# SDP21_Daughter_Board_Schematic_REV1.net
KiCad netlist of a schematic drawn in Altium Designer
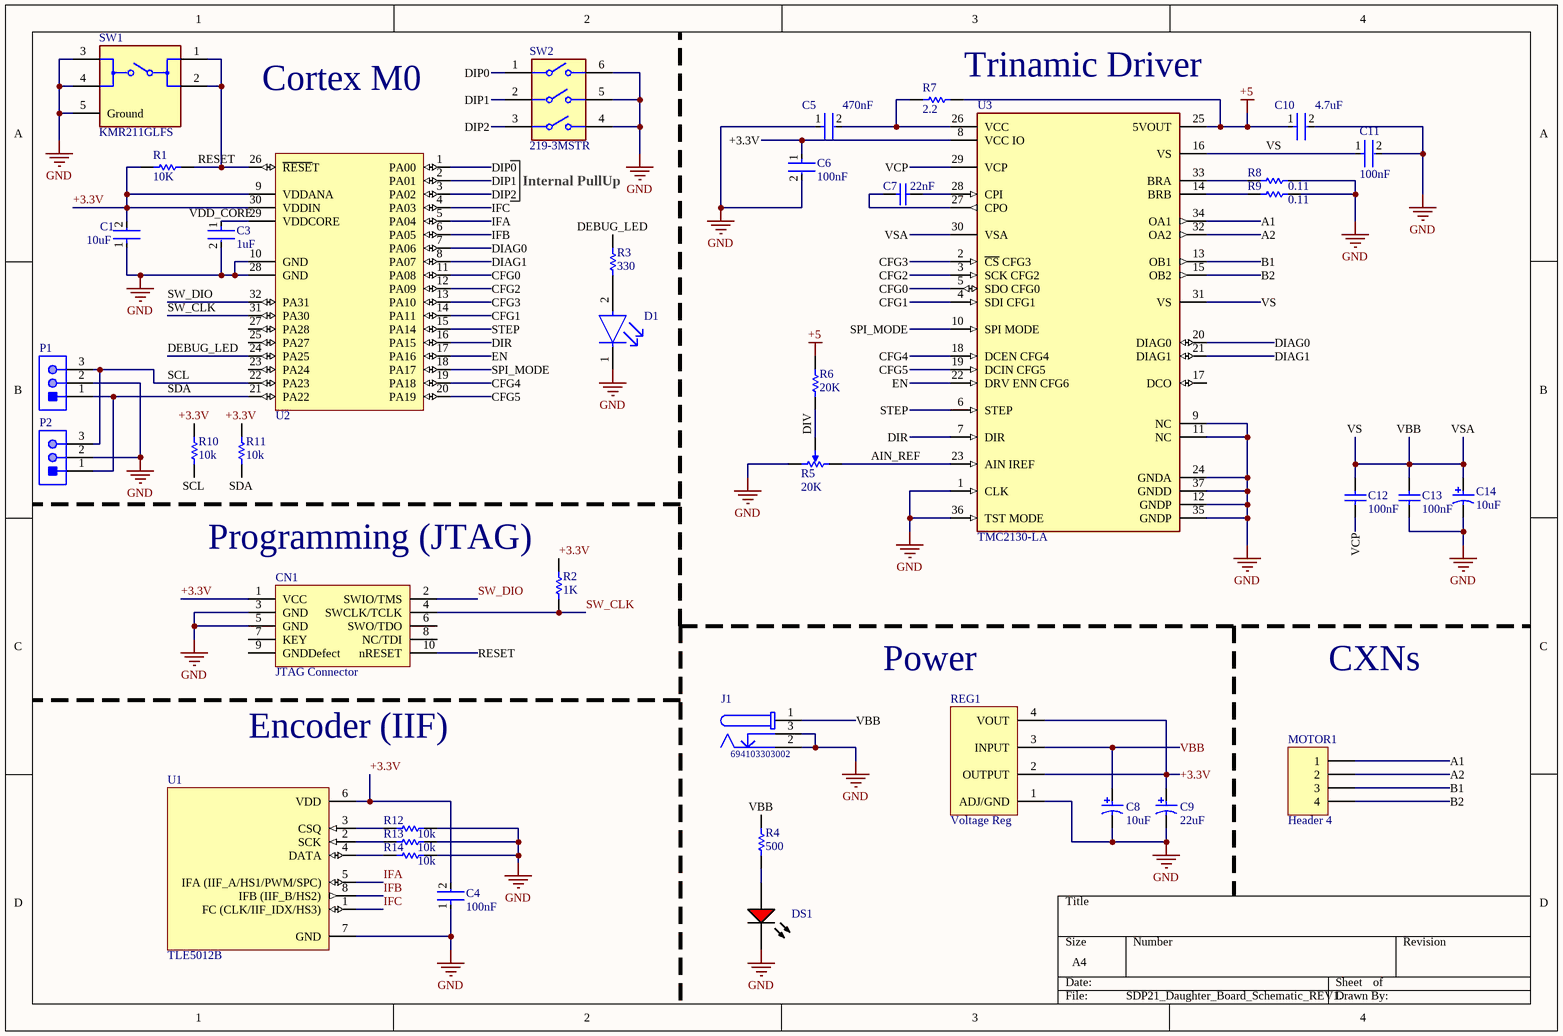
[diagram p0: SDP21_Daughter_Board_Schematic_REV1.SchDoc]

(export (version "E")
  (design (tool "Eeschema 10.0.6"))
  (components
    (comp (ref "C1")
      (value "10uF")
      (footprint "FP-GRM188-0_1-e0_2_0_55-IPC_A")
      (description "Chip Multilayer Ceramic Capacitors for General Purpose, 0603, 10uF, X5R, 15%, 20%, 6.3V")
      (fields (field (name "VOLTAGE") "6.3V") (field (name "TOLERANCE") "20%"))
      (libsource (lib "Altium Content Vault") (part "02cd4be3c70576c341d710602a673aa"))
    )
    (comp (ref "C3")
      (value "1uF")
      (footprint "FP-CC0603-DA-MFG")
      (description "CAP CER 1UF 16V X7R 0603")
      (fields (field (name "TOLERANCE") "0.1") (field (name "MANUFACTURER") "YAGEO"))
      (libsource (lib "Altium Content Vault") (part "11868f565c42a9108669ba33697ecf6"))
    )
    (comp (ref "C4")
      (value "100nF")
      (footprint "FP-CGA3E-0_3-0_1-IPC_A")
      (description "Cap Ceramic 100nF 50V X7R 10% Pad SMD 0603 +125°C Automotive T/R")
      (fields (field (name "VOLTAGE") "50V") (field (name "TOLERANCE") "10%"))
      (libsource (lib "Altium Content Vault") (part "b4654b650e69147ec39a6b967a45e02"))
    )
    (comp (ref "C5")
      (value "470nF")
      (footprint "FP-CC0603-DA-MFG")
      (description "CAP CER 0.47UF 10V X7R 0603")
      (fields (field (name "MANUFACTURER PART NUMBER") "CC0603KRX7R6BB474") (field (name "TOLERANCE") "0.1"))
      (libsource (lib "Altium Content Vault") (part "11868f565c42a9108669ba33697ecf6"))
    )
    (comp (ref "C6")
      (value "100nF")
      (footprint "FP-CGA3E-0_3-0_1-IPC_A")
      (description "Cap Ceramic 100nF 100V X7S 10% Pad SMD 0603 +125°C Automotive T/R")
      (fields (field (name "TOLERANCE") "10%"))
      (libsource (lib "Altium Content Vault") (part "b4654b650e69147ec39a6b967a45e02"))
    )
    (comp (ref "C7")
      (value "22nF")
      (footprint "CAPC1608X90X35ML10T15")
      (fields (field (name "MANUFACTURER") "Murata") (field (name "PART NUMBER") "GRM188R71H223KA01D"))
      (libsource (lib "Altium Content Vault") (part "CAP"))
    )
    (comp (ref "C8")
      (value "10uF")
      (footprint "KEMT-A-3216-18-2_M")
      (description "Capacitor, Tantalum, 10 uF, +/- 10%, 10 V, -55 to 125 degC, 2-Pin SMD (1206), RoHS, Tape and Reel")
      (fields (field (name "TOLERANCE") "±10%") (field (name "MANUFACTURER") "Kemet"))
      (libsource (lib "Altium Content Vault") (part "CAP-P-2"))
    )
    (comp (ref "C9")
      (value "22uF")
      (footprint "AVX-TAJ-A-2_L")
      (description "Chip Capacitor, 22 uF, +/- 10%, 10 V, -55 to 125 degC, 1206 (3216 Metric), RoHS, Tape and Reel")
      (fields (field (name "MANUFACTURER") "AVX") (field (name "TOLERANCE") "10%"))
      (libsource (lib "Altium Content Vault") (part "CAP-P-2"))
    )
    (comp (ref "C10")
      (value "4.7uF")
      (footprint "FP-GRM188-0_15-IPC_C")
      (description "Chip Multilayer Ceramic Capacitors for General Purpose, 0603, 4.7uF, X5R, 15%, 10%, 25V")
      (fields (field (name "VOLTAGE") "25V") (field (name "TOLERANCE") "10%"))
      (libsource (lib "Altium Content Vault") (part "02cd4be3c70576c341d710602a673aa"))
    )
    (comp (ref "C11")
      (value "100nF")
      (footprint "FP-CGA3E-0_3-0_1-IPC_A")
      (description "Cap Ceramic 100nF 100V X7S 10% Pad SMD 0603 +125°C Automotive T/R")
      (fields (field (name "TOLERANCE") "10%"))
      (libsource (lib "Altium Content Vault") (part "b4654b650e69147ec39a6b967a45e02"))
    )
    (comp (ref "C12")
      (value "100nF")
      (footprint "CAPC1608X90X35ML10T15")
      (description "Chip Capacitor, 0.1 uF, +/- 10%, 50 V, -55 to 125 degC, 0603 (1608 Metric), RoHS, Tape and Reel")
      (fields (field (name "TOLERANCE") "10%") (field (name "VOLTAGE") "50V"))
      (libsource (lib "Altium Content Vault") (part "CAP-NP-2"))
    )
    (comp (ref "C13")
      (value "100nF")
      (footprint "CAPC1608X90X35ML10T15")
      (description "Chip Capacitor, 0.1 uF, +/- 10%, 50 V, -55 to 125 degC, 0603 (1608 Metric), RoHS, Tape and Reel")
      (fields (field (name "TOLERANCE") "10%") (field (name "VOLTAGE") "50V"))
      (libsource (lib "Altium Content Vault") (part "CAP-NP-2"))
    )
    (comp (ref "C14")
      (value "10uF")
      (footprint "NIC-CAPA2-6.3X5.8_V")
      (fields (field (name "MANUFACTURER") "Nichicon") (field (name "PARTNUMBER") "UUD1H100MCL1GS"))
      (libsource (lib "Altium Content Vault") (part "NIC-CAP-P-2"))
    )
    (comp (ref "CN1")
      (value "JTAG Connector")
      (footprint "Header 5x2 - 50mil")
      (libsource (lib "SDP21_Symbols") (part "JTAG Connector"))
    )
    (comp (ref "D1")
      (value "APT1608LZGCK")
      (footprint "FP-APT1608LZGCK-MFG")
      (description "LED GREEN CLEAR 2SMD")
      (libsource (lib "Altium Content Vault") (part "8706943c75ba83719d021d2fdc84c58"))
    )
    (comp (ref "DS1")
      (value "TLMS1100-GS08")
      (footprint "VISH-TLMX1100_V")
      (description "LED, RED, 2.1 V, -40 to 100 degC, 2-Pin SMD (0603), RoHS, Tape and Reel")
      (fields (field (name "TOLERANCE") "5%"))
      (libsource (lib "Altium Content Vault") (part "LED-RED-AK-2"))
    )
    (comp (ref "J1")
      (value "694103303002")
      (footprint "694103303002")
      (description "DC Power Jack Connector WR-DC, Male, Right Angled, THT, 2 A, 30 V")
      (fields (field (name "MANUFACTURER") "Wurth Elektronik") (field (name "PUBLISHER") "WurthElektronik"))
      (libsource (lib "Altium Content Vault") (part "WE-JACK-2CD3-RN"))
    )
    (comp (ref "MOTOR1")
      (value "Header 4")
      (footprint "HDR1X4")
      (description "Header, 4-Pin")
      (fields (field (name "PUBLISHER") "Altium Limited"))
      (libsource (lib "Miscellaneous Connectors") (part "Header 4"))
    )
    (comp (ref "P1")
      (value "B3B-PH-K-S(LF)(SN)")
      (footprint "JST-B3B-PH-K-S-3_V")
      (fields (field (name "MANUFACTURER") "JST"))
      (libsource (lib "Altium Content Vault") (part "CN-1P-M-R3"))
    )
    (comp (ref "P2")
      (value "B3B-PH-K-S(LF)(SN)")
      (footprint "JST-B3B-PH-K-S-3_V")
      (fields (field (name "MANUFACTURER") "JST"))
      (libsource (lib "Altium Content Vault") (part "CN-1P-M-R3"))
    )
    (comp (ref "R1")
      (value "10K")
      (footprint "RESC1609X55X30LL15T15")
      (description "Chip Resistor, 10 KOhm, +/- 1%, 0.1 W, -55 to 155 degC, 0603 (1608 Metric), RoHS, Tape and Reel")
      (fields (field (name "TOLERANCE") "1%") (field (name "MANUFACTURER") "Panasonic"))
      (libsource (lib "Altium Content Vault") (part "RES-2"))
    )
    (comp (ref "R2")
      (value "1K")
      (footprint "RESC1608X55X30LL20T20")
      (fields (field (name "MANUFACTURER") "Panasonic") (field (name "PART NUMBER") "ERA3AEB102V"))
      (libsource (lib "Altium Content Vault") (part "RES"))
    )
    (comp (ref "R3")
      (value "330")
      (footprint "RESC1608X55X30ML15T15")
      (fields (field (name "MANUFACTURER") "Panasonic") (field (name "PART NUMBER") "ERJ-3RSJR10V"))
      (libsource (lib "Altium Content Vault") (part "RES"))
    )
    (comp (ref "R4")
      (value "500")
      (footprint "RESC1608X55X30ML15T15")
      (fields (field (name "MANUFACTURER") "Panasonic") (field (name "PART NUMBER") "ERJ-3RSJR10V"))
      (libsource (lib "Altium Content Vault") (part "RES"))
    )
    (comp (ref "R5")
      (value "20K")
      (footprint "BOUR-3313J-1_V")
      (fields (field (name "MANUFACTURER") "Bourns") (field (name "TOLERANCE") "±20%"))
      (libsource (lib "Altium Content Vault") (part "RES-ADJ-3_A"))
    )
    (comp (ref "R6")
      (value "20K")
      (footprint "RESC1608X55X25LL10T15")
      (description "Chip Resistor, 20 KOhm, +/- 1%, 0.1 W, -55 to 155 degC, 0603 (1608 Metric), RoHS, Tape and Reel")
      (fields (field (name "MANUFACTURER") "Yageo") (field (name "TOLERANCE") "1%"))
      (libsource (lib "Altium Content Vault") (part "RES-2"))
    )
    (comp (ref "R7")
      (value "2.2")
      (footprint "RESC1608X55X30ML15T15")
      (fields (field (name "MANUFACTURER") "Panasonic") (field (name "PART NUMBER") "ERJ-3RSJR10V"))
      (libsource (lib "Altium Content Vault") (part "RES"))
    )
    (comp (ref "R8")
      (value "0.11")
      (footprint "RESC3116X65X40ML10T20")
      (fields (field (name "PART NUMBER") "RL1206FR-7W0R56L") (field (name "MANUFACTURER") "Yageo"))
      (libsource (lib "Altium Content Vault") (part "RES"))
    )
    (comp (ref "R9")
      (value "0.11")
      (footprint "RESC3116X65X40ML10T20")
      (fields (field (name "PART NUMBER") "RL1206FR-7W0R56L") (field (name "MANUFACTURER") "Yageo"))
      (libsource (lib "Altium Content Vault") (part "RES"))
    )
    (comp (ref "R10")
      (value "10k")
      (footprint "RESC1608X55X30ML15T15")
      (fields (field (name "MANUFACTURER") "Panasonic") (field (name "PART NUMBER") "ERJ-3RSJR10V"))
      (libsource (lib "Altium Content Vault") (part "RES"))
    )
    (comp (ref "R11")
      (value "10k")
      (footprint "RESC1608X55X30ML15T15")
      (fields (field (name "MANUFACTURER") "Panasonic") (field (name "PART NUMBER") "ERJ-3RSJR10V"))
      (libsource (lib "Altium Content Vault") (part "RES"))
    )
    (comp (ref "R12")
      (value "10k")
      (footprint "RESC1608X55X30ML15T15")
      (fields (field (name "MANUFACTURER") "Panasonic") (field (name "PART NUMBER") "ERJ-3RSJR10V"))
      (libsource (lib "Altium Content Vault") (part "RES"))
    )
    (comp (ref "R13")
      (value "10k")
      (footprint "RESC1608X55X30ML15T15")
      (fields (field (name "MANUFACTURER") "Panasonic") (field (name "PART NUMBER") "ERJ-3RSJR10V"))
      (libsource (lib "Altium Content Vault") (part "RES"))
    )
    (comp (ref "R14")
      (value "10k")
      (footprint "RESC1608X55X30ML15T15")
      (fields (field (name "MANUFACTURER") "Panasonic") (field (name "PART NUMBER") "ERJ-3RSJR10V"))
      (libsource (lib "Altium Content Vault") (part "RES"))
    )
    (comp (ref "REG1")
      (value "Voltage Reg")
      (footprint "SOT223")
      (libsource (lib "SDP21_Symbols") (part "Voltage Reg"))
    )
    (comp (ref "SW1")
      (value "KMR211GLFS")
      (footprint "FP-KMR211GLFS-MFG")
      (description "SWITCH TACTILE SPST-NO 0.05A 32V")
      (libsource (lib "Altium Content Vault") (part "99988cc0f9d3d39bd794ae22da860e5"))
    )
    (comp (ref "SW2")
      (value "219-3MSTR")
      (footprint "FP-219-3MSTR-MFG")
      (description "SWITCH SLIDE DIP SPST 100MA 20V")
      (libsource (lib "Altium Content Vault") (part "7c490946f25aa2bb1cd4cef5bc3ec4e"))
    )
    (comp (ref "U1")
      (value "TLE5012B")
      (footprint "PG-DSO-8")
      (description "TLE5012B GMR-Based Angle Sensor PG-DSO-8")
      (libsource (lib "SDP21_Symbols") (part "TLE5012B"))
    )
    (comp (ref "U2")
      (value "ATSAMD21E15B-AUT")
      (footprint "TQFP-32")
      (description "IC MCU 32BIT 32KB FLASH 32TQFP")
      (libsource (lib "SDP21_Symbols") (part "ATSAMD21E15B-AUT"))
    )
    (comp (ref "U3")
      (value "TMC2130-LA")
      (footprint "FP-TMC2130-LA-IPC_C")
      (description "IC MTR DRV BIPOLAR 5.5-46V 36QFN")
      (fields
        (field (name "MANUFACTURER") "Trinamic")
        (field (name "OCTOPART") "https://octopart.com/tmc2130-la-trinamic-61933290")
      )
      (libsource (lib "Altium Content Vault") (part "e15e8a1811453f9845eeab93ec44087"))
    )
  )
  (nets
    (net (code "1") (name "+5") (class "Default")
      (node (ref "C10") (pin "1") (pinfunction "1_1") (pintype "passive"))
      (node (ref "R6") (pin "2") (pinfunction "2_2") (pintype "passive"))
      (node (ref "R7") (pin "2") (pinfunction "2_2") (pintype "passive"))
      (node (ref "U3") (pin "25") (pinfunction "5VOUT_25") (pintype "power_in"))
    )
    (net (code "2") (name "/+3.3V") (class "Default")
      (node (ref "C1") (pin "2") (pinfunction "2_2") (pintype "passive"))
      (node (ref "C4") (pin "2") (pinfunction "2_2") (pintype "passive"))
      (node (ref "C6") (pin "1") (pinfunction "1_1") (pintype "passive"))
      (node (ref "C9") (pin "1") (pinfunction "1_1") (pintype "passive"))
      (node (ref "CN1") (pin "1") (pinfunction "VCC_1") (pintype "power_in"))
      (node (ref "R1") (pin "1") (pinfunction "1_1") (pintype "passive"))
      (node (ref "R10") (pin "2") (pinfunction "2_2") (pintype "passive"))
      (node (ref "R11") (pin "2") (pinfunction "2_2") (pintype "passive"))
      (node (ref "R2") (pin "2") (pinfunction "2_2") (pintype "passive"))
      (node (ref "REG1") (pin "2") (pinfunction "OUTPUT_2") (pintype "passive"))
      (node (ref "REG1") (pin "4") (pinfunction "VOUT_4") (pintype "passive"))
      (node (ref "U1") (pin "6") (pinfunction "VDD_6") (pintype "power_in"))
      (node (ref "U2") (pin "30") (pinfunction "VDDIN_30") (pintype "power_in"))
      (node (ref "U2") (pin "9") (pinfunction "VDDANA_9") (pintype "power_in"))
      (node (ref "U3") (pin "8") (pinfunction "VCC_IO_8") (pintype "power_in"))
    )
    (net (code "3") (name "/A1") (class "Default")
      (node (ref "MOTOR1") (pin "1") (pinfunction "1_1") (pintype "passive"))
      (node (ref "U3") (pin "34") (pinfunction "OA1_34") (pintype "output"))
    )
    (net (code "4") (name "/A2") (class "Default")
      (node (ref "MOTOR1") (pin "2") (pinfunction "2_2") (pintype "passive"))
      (node (ref "U3") (pin "32") (pinfunction "OA2_32") (pintype "output"))
    )
    (net (code "5") (name "/AIN_REF") (class "Default")
      (node (ref "R5") (pin "1") (pinfunction "1_1") (pintype "passive"))
      (node (ref "U3") (pin "23") (pinfunction "AIN_IREF_23") (pintype "input"))
    )
    (net (code "6") (name "/B1") (class "Default")
      (node (ref "MOTOR1") (pin "3") (pinfunction "3_3") (pintype "passive"))
      (node (ref "U3") (pin "13") (pinfunction "OB1_13") (pintype "output"))
    )
    (net (code "7") (name "/B2") (class "Default")
      (node (ref "MOTOR1") (pin "4") (pinfunction "4_4") (pintype "passive"))
      (node (ref "U3") (pin "15") (pinfunction "OB2_15") (pintype "output"))
    )
    (net (code "8") (name "/CFG0") (class "Default")
      (node (ref "U2") (pin "11") (pinfunction "PA08_11") (pintype "bidirectional"))
      (node (ref "U3") (pin "5") (pinfunction "SDO_CFG0_5") (pintype "bidirectional"))
    )
    (net (code "9") (name "/CFG1") (class "Default")
      (node (ref "U2") (pin "14") (pinfunction "PA11_14") (pintype "bidirectional"))
      (node (ref "U3") (pin "4") (pinfunction "SDI_CFG1_4") (pintype "input"))
    )
    (net (code "10") (name "/CFG2") (class "Default")
      (node (ref "U2") (pin "12") (pinfunction "PA09_12") (pintype "bidirectional"))
      (node (ref "U3") (pin "3") (pinfunction "SCK_CFG2_3") (pintype "input"))
    )
    (net (code "11") (name "/CFG3") (class "Default")
      (node (ref "U2") (pin "13") (pinfunction "PA10_13") (pintype "bidirectional"))
      (node (ref "U3") (pin "2") (pinfunction "~{CS}_CFG3_2") (pintype "input"))
    )
    (net (code "12") (name "/CFG4") (class "Default")
      (node (ref "U2") (pin "19") (pinfunction "PA18_19") (pintype "bidirectional"))
      (node (ref "U3") (pin "18") (pinfunction "DCEN_CFG4_18") (pintype "input"))
    )
    (net (code "13") (name "/CFG5") (class "Default")
      (node (ref "U2") (pin "20") (pinfunction "PA19_20") (pintype "bidirectional"))
      (node (ref "U3") (pin "19") (pinfunction "DCIN_CFG5_19") (pintype "input"))
    )
    (net (code "14") (name "/DEBUG_LED") (class "Default")
      (node (ref "R3") (pin "2") (pinfunction "2_2") (pintype "passive"))
      (node (ref "U2") (pin "24") (pinfunction "PA25_24") (pintype "bidirectional"))
    )
    (net (code "15") (name "/DIAG0") (class "Default")
      (node (ref "U2") (pin "7") (pinfunction "PA06_7") (pintype "bidirectional"))
      (node (ref "U3") (pin "20") (pinfunction "DIAG0_20") (pintype "bidirectional"))
    )
    (net (code "16") (name "/DIAG1") (class "Default")
      (node (ref "U2") (pin "8") (pinfunction "PA07_8") (pintype "bidirectional"))
      (node (ref "U3") (pin "21") (pinfunction "DIAG1_21") (pintype "bidirectional"))
    )
    (net (code "17") (name "/DIP0") (class "Default")
      (node (ref "SW2") (pin "1") (pinfunction "1_1") (pintype "passive"))
      (node (ref "U2") (pin "1") (pinfunction "PA00_1") (pintype "bidirectional"))
    )
    (net (code "18") (name "/DIP1") (class "Default")
      (node (ref "SW2") (pin "2") (pinfunction "2_2") (pintype "passive"))
      (node (ref "U2") (pin "2") (pinfunction "PA01_2") (pintype "bidirectional"))
    )
    (net (code "19") (name "/DIP2") (class "Default")
      (node (ref "SW2") (pin "3") (pinfunction "3_3") (pintype "passive"))
      (node (ref "U2") (pin "3") (pinfunction "PA02_3") (pintype "bidirectional"))
    )
    (net (code "20") (name "/DIR") (class "Default")
      (node (ref "U2") (pin "16") (pinfunction "PA15_16") (pintype "bidirectional"))
      (node (ref "U3") (pin "7") (pinfunction "DIR_7") (pintype "input"))
    )
    (net (code "21") (name "/DIV") (class "Default")
      (node (ref "R5") (pin "2") (pinfunction "2_2") (pintype "passive"))
      (node (ref "R6") (pin "1") (pinfunction "1_1") (pintype "passive"))
    )
    (net (code "22") (name "/EN") (class "Default")
      (node (ref "U2") (pin "17") (pinfunction "PA16_17") (pintype "bidirectional"))
      (node (ref "U3") (pin "22") (pinfunction "DRV_ENN_CFG6_22") (pintype "input"))
    )
    (net (code "23") (name "/IFA") (class "Default")
      (node (ref "U1") (pin "5") (pinfunction "IFA_(IIF_A/HS1/PWM/SPC)_5") (pintype "bidirectional"))
      (node (ref "U2") (pin "5") (pinfunction "PA04_5") (pintype "bidirectional"))
    )
    (net (code "24") (name "/IFB") (class "Default")
      (node (ref "U1") (pin "8") (pinfunction "IFB_(IIF_B/HS2)_8") (pintype "output"))
      (node (ref "U2") (pin "6") (pinfunction "PA05_6") (pintype "bidirectional"))
    )
    (net (code "25") (name "/IFC") (class "Default")
      (node (ref "U1") (pin "1") (pinfunction "FC_(CLK/IIF_IDX/HS3)_1") (pintype "bidirectional"))
      (node (ref "U2") (pin "4") (pinfunction "PA03_4") (pintype "bidirectional"))
    )
    (net (code "26") (name "/RESET") (class "Default")
      (node (ref "CN1") (pin "10") (pinfunction "nRESET_10") (pintype "power_in"))
      (node (ref "R1") (pin "2") (pinfunction "2_2") (pintype "passive"))
      (node (ref "SW1") (pin "1") (pinfunction "1_1") (pintype "passive"))
      (node (ref "SW1") (pin "2") (pinfunction "2_2") (pintype "passive"))
      (node (ref "U2") (pin "26") (pinfunction "~{RESE}T_26") (pintype "bidirectional"))
    )
    (net (code "27") (name "/SCL") (class "Default")
      (node (ref "P1") (pin "3") (pinfunction "3_3") (pintype "passive"))
      (node (ref "P2") (pin "3") (pinfunction "3_3") (pintype "passive"))
      (node (ref "R10") (pin "1") (pinfunction "1_1") (pintype "passive"))
      (node (ref "U2") (pin "22") (pinfunction "PA23_22") (pintype "bidirectional"))
    )
    (net (code "28") (name "/SDA") (class "Default")
      (node (ref "P1") (pin "1") (pinfunction "1_1") (pintype "passive"))
      (node (ref "P2") (pin "1") (pinfunction "1_1") (pintype "passive"))
      (node (ref "R11") (pin "1") (pinfunction "1_1") (pintype "passive"))
      (node (ref "U2") (pin "21") (pinfunction "PA22_21") (pintype "bidirectional"))
    )
    (net (code "29") (name "/SPI_MODE") (class "Default")
      (node (ref "U2") (pin "18") (pinfunction "PA17_18") (pintype "bidirectional"))
      (node (ref "U3") (pin "10") (pinfunction "SPI_MODE_10") (pintype "input"))
    )
    (net (code "30") (name "/STEP") (class "Default")
      (node (ref "U2") (pin "15") (pinfunction "PA14_15") (pintype "bidirectional"))
      (node (ref "U3") (pin "6") (pinfunction "STEP_6") (pintype "input"))
    )
    (net (code "31") (name "/SW_CLK") (class "Default")
      (node (ref "CN1") (pin "4") (pinfunction "SWCLK/TCLK_4") (pintype "power_in"))
      (node (ref "R2") (pin "1") (pinfunction "1_1") (pintype "passive"))
      (node (ref "U2") (pin "31") (pinfunction "PA30_31") (pintype "bidirectional"))
    )
    (net (code "32") (name "/SW_DIO") (class "Default")
      (node (ref "CN1") (pin "2") (pinfunction "SWIO/TMS_2") (pintype "power_in"))
      (node (ref "U2") (pin "32") (pinfunction "PA31_32") (pintype "bidirectional"))
    )
    (net (code "33") (name "/VBB") (class "Default")
      (node (ref "C11") (pin "1") (pinfunction "1_1") (pintype "passive"))
      (node (ref "C12") (pin "2") (pinfunction "2_2") (pintype "passive"))
      (node (ref "C13") (pin "2") (pinfunction "2_2") (pintype "passive"))
      (node (ref "C14") (pin "1") (pinfunction "1_1") (pintype "passive"))
      (node (ref "C8") (pin "1") (pinfunction "1_1") (pintype "passive"))
      (node (ref "J1") (pin "1") (pinfunction "1_1") (pintype "passive"))
      (node (ref "R4") (pin "2") (pinfunction "2_2") (pintype "passive"))
      (node (ref "REG1") (pin "3") (pinfunction "INPUT_3") (pintype "passive"))
      (node (ref "U3") (pin "16") (pinfunction "VS_16") (pintype "power_in"))
      (node (ref "U3") (pin "30") (pinfunction "VSA_30") (pintype "power_in"))
      (node (ref "U3") (pin "31") (pinfunction "VS_31") (pintype "power_in"))
    )
    (net (code "34") (name "/VCP") (class "Default")
      (node (ref "C12") (pin "1") (pinfunction "1_1") (pintype "passive"))
      (node (ref "U3") (pin "29") (pinfunction "VCP_29") (pintype "power_in"))
    )
    (net (code "35") (name "/VDD_CORE") (class "Default")
      (node (ref "C3") (pin "1") (pinfunction "1_1") (pintype "passive"))
      (node (ref "U2") (pin "29") (pinfunction "VDDCORE_29") (pintype "power_in"))
    )
    (net (code "36") (name "GND") (class "Default")
      (node (ref "C1") (pin "1") (pinfunction "1_1") (pintype "passive"))
      (node (ref "C10") (pin "2") (pinfunction "2_2") (pintype "passive"))
      (node (ref "C11") (pin "2") (pinfunction "2_2") (pintype "passive"))
      (node (ref "C13") (pin "1") (pinfunction "1_1") (pintype "passive"))
      (node (ref "C14") (pin "2") (pinfunction "2_2") (pintype "passive"))
      (node (ref "C3") (pin "2") (pinfunction "2_2") (pintype "passive"))
      (node (ref "C4") (pin "1") (pinfunction "1_1") (pintype "passive"))
      (node (ref "C5") (pin "1") (pinfunction "1_1") (pintype "passive"))
      (node (ref "C6") (pin "2") (pinfunction "2_2") (pintype "passive"))
      (node (ref "C8") (pin "2") (pinfunction "2_2") (pintype "passive"))
      (node (ref "C9") (pin "2") (pinfunction "2_2") (pintype "passive"))
      (node (ref "CN1") (pin "3") (pinfunction "GND_3") (pintype "power_in"))
      (node (ref "CN1") (pin "5") (pinfunction "GND_5") (pintype "power_in"))
      (node (ref "D1") (pin "1") (pinfunction "C_1") (pintype "passive"))
      (node (ref "DS1") (pin "2") (pinfunction "K_2") (pintype "passive"))
      (node (ref "J1") (pin "2") (pinfunction "2_2") (pintype "passive"))
      (node (ref "J1") (pin "3") (pinfunction "3_3") (pintype "passive"))
      (node (ref "P1") (pin "2") (pinfunction "2_2") (pintype "passive"))
      (node (ref "P2") (pin "2") (pinfunction "2_2") (pintype "passive"))
      (node (ref "R12") (pin "1") (pinfunction "1_1") (pintype "passive"))
      (node (ref "R13") (pin "1") (pinfunction "1_1") (pintype "passive"))
      (node (ref "R14") (pin "1") (pinfunction "1_1") (pintype "passive"))
      (node (ref "R5") (pin "3") (pinfunction "3_3") (pintype "passive"))
      (node (ref "R8") (pin "2") (pinfunction "2_2") (pintype "passive"))
      (node (ref "R9") (pin "2") (pinfunction "2_2") (pintype "passive"))
      (node (ref "REG1") (pin "1") (pinfunction "ADJ/GND_1") (pintype "passive"))
      (node (ref "SW1") (pin "3") (pinfunction "3_3") (pintype "passive"))
      (node (ref "SW1") (pin "4") (pinfunction "4_4") (pintype "passive"))
      (node (ref "SW1") (pin "5") (pinfunction "Ground_5") (pintype "power_in"))
      (node (ref "SW2") (pin "4") (pinfunction "4_4") (pintype "passive"))
      (node (ref "SW2") (pin "5") (pinfunction "5_5") (pintype "passive"))
      (node (ref "SW2") (pin "6") (pinfunction "6_6") (pintype "passive"))
      (node (ref "U1") (pin "7") (pinfunction "GND_7") (pintype "power_in"))
      (node (ref "U2") (pin "10") (pinfunction "GND_10") (pintype "power_in"))
      (node (ref "U2") (pin "28") (pinfunction "GND_28") (pintype "power_in"))
      (node (ref "U3") (pin "1") (pinfunction "CLK_1") (pintype "input"))
      (node (ref "U3") (pin "11") (pinfunction "NC_11") (pintype "passive"))
      (node (ref "U3") (pin "12") (pinfunction "GNDP_12") (pintype "power_in"))
      (node (ref "U3") (pin "24") (pinfunction "GNDA_24") (pintype "power_in"))
      (node (ref "U3") (pin "35") (pinfunction "GNDP_35") (pintype "power_in"))
      (node (ref "U3") (pin "36") (pinfunction "TST_MODE_36") (pintype "input"))
      (node (ref "U3") (pin "37") (pinfunction "GNDD_37") (pintype "power_in"))
      (node (ref "U3") (pin "9") (pinfunction "NC_9") (pintype "passive"))
    )
    (net (code "37") (name "Net-(D1-A)") (class "Default")
      (node (ref "D1") (pin "2") (pinfunction "A_2") (pintype "passive"))
      (node (ref "R3") (pin "1") (pinfunction "1_1") (pintype "passive"))
    )
    (net (code "38") (name "Net-(DS1-A)") (class "Default")
      (node (ref "DS1") (pin "1") (pinfunction "A_1") (pintype "passive"))
      (node (ref "R4") (pin "1") (pinfunction "1_1") (pintype "passive"))
    )
    (net (code "39") (name "Net-(U1-CSQ)") (class "Default")
      (node (ref "R12") (pin "2") (pinfunction "2_2") (pintype "passive"))
      (node (ref "U1") (pin "3") (pinfunction "CSQ_3") (pintype "input"))
    )
    (net (code "40") (name "Net-(U1-DATA)") (class "Default")
      (node (ref "R14") (pin "2") (pinfunction "2_2") (pintype "passive"))
      (node (ref "U1") (pin "4") (pinfunction "DATA_4") (pintype "bidirectional"))
    )
    (net (code "41") (name "Net-(U1-SCK)") (class "Default")
      (node (ref "R13") (pin "2") (pinfunction "2_2") (pintype "passive"))
      (node (ref "U1") (pin "2") (pinfunction "SCK_2") (pintype "input"))
    )
    (net (code "42") (name "Net-(U3-BRA)") (class "Default")
      (node (ref "R8") (pin "1") (pinfunction "1_1") (pintype "passive"))
      (node (ref "U3") (pin "33") (pinfunction "BRA_33") (pintype "passive"))
    )
    (net (code "43") (name "Net-(U3-BRB)") (class "Default")
      (node (ref "R9") (pin "1") (pinfunction "1_1") (pintype "passive"))
      (node (ref "U3") (pin "14") (pinfunction "BRB_14") (pintype "passive"))
    )
    (net (code "44") (name "Net-(U3-CPI)") (class "Default")
      (node (ref "C7") (pin "2") (pinfunction "2_2") (pintype "passive"))
      (node (ref "U3") (pin "28") (pinfunction "CPI_28") (pintype "input"))
    )
    (net (code "45") (name "Net-(U3-CPO)") (class "Default")
      (node (ref "C7") (pin "1") (pinfunction "1_1") (pintype "passive"))
      (node (ref "U3") (pin "27") (pinfunction "CPO_27") (pintype "output"))
    )
    (net (code "46") (name "Net-(U3-VCC)") (class "Default")
      (node (ref "C5") (pin "2") (pinfunction "2_2") (pintype "passive"))
      (node (ref "R7") (pin "1") (pinfunction "1_1") (pintype "passive"))
      (node (ref "U3") (pin "26") (pinfunction "VCC_26") (pintype "power_in"))
    )
    (net (code "47") (name "unconnected-(CN1-GNDDefect-Pad9)") (class "Default")
      (node (ref "CN1") (pin "9") (pinfunction "GNDDefect_9") (pintype "power_in"))
    )
    (net (code "48") (name "unconnected-(CN1-KEY-Pad7)") (class "Default")
      (node (ref "CN1") (pin "7") (pinfunction "KEY_7") (pintype "power_in"))
    )
    (net (code "49") (name "unconnected-(CN1-NC{slash}TDI-Pad8)") (class "Default")
      (node (ref "CN1") (pin "8") (pinfunction "NC/TDI_8") (pintype "power_in"))
    )
    (net (code "50") (name "unconnected-(CN1-SWO{slash}TDO-Pad6)") (class "Default")
      (node (ref "CN1") (pin "6") (pinfunction "SWO/TDO_6") (pintype "power_in"))
    )
    (net (code "51") (name "unconnected-(U2-PA24-Pad23)") (class "Default")
      (node (ref "U2") (pin "23") (pinfunction "PA24_23") (pintype "bidirectional"))
    )
    (net (code "52") (name "unconnected-(U2-PA27-Pad25)") (class "Default")
      (node (ref "U2") (pin "25") (pinfunction "PA27_25") (pintype "bidirectional"))
    )
    (net (code "53") (name "unconnected-(U2-PA28-Pad27)") (class "Default")
      (node (ref "U2") (pin "27") (pinfunction "PA28_27") (pintype "bidirectional"))
    )
    (net (code "54") (name "unconnected-(U3-DCO-Pad17)") (class "Default")
      (node (ref "U3") (pin "17") (pinfunction "DCO_17") (pintype "bidirectional"))
    )
  )
)
